# led.net
KiCad netlist of a schematic drawn in Altium Designer
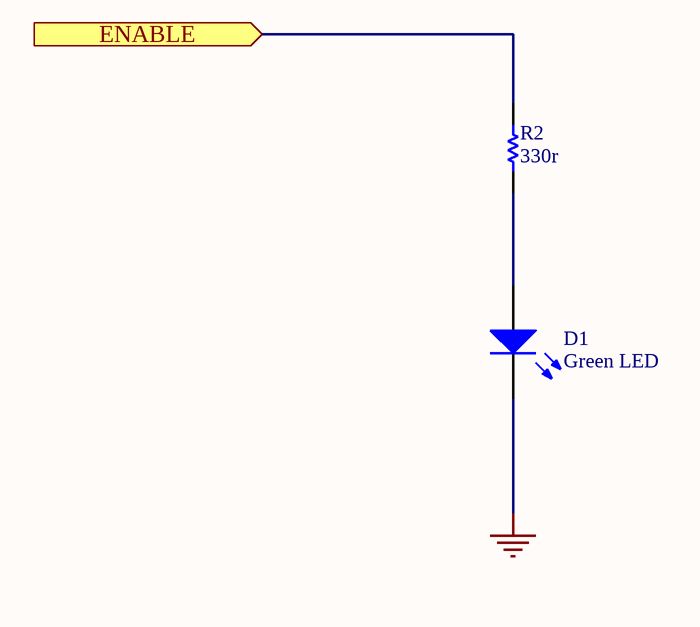
[diagram p0: led.SchDoc]

(export (version "E")
  (design (tool "Eeschema 10.0.6"))
  (components
    (comp (ref "D1")
      (value "Green LED")
      (footprint "LED-0")
      (description "Typical INFRARED GaAs LED")
      (fields (field (name "PUBLISHER") "Altium Limited"))
      (libsource (lib "Miscellaneous Devices") (part "LED0"))
    )
    (comp (ref "R2")
      (value "330r")
      (footprint "AXIAL-0.3")
      (description "Resistor")
      (fields (field (name "PUBLISHER") "Altium Limited"))
      (libsource (lib "Miscellaneous Devices") (part "Res1"))
    )
  )
  (nets
    (net (code "1") (name "/ENABLE") (class "Default")
      (node (ref "R2") (pin "2") (pinfunction "2_2") (pintype "passive"))
    )
    (net (code "2") (name "GND") (class "Default")
      (node (ref "D1") (pin "2") (pinfunction "K_2") (pintype "passive"))
    )
    (net (code "3") (name "Net-(D1-A)") (class "Default")
      (node (ref "D1") (pin "1") (pinfunction "A_1") (pintype "passive"))
      (node (ref "R2") (pin "1") (pinfunction "1_1") (pintype "passive"))
    )
  )
)
